# Root.net
KiCad netlist of a schematic drawn in Altium Designer
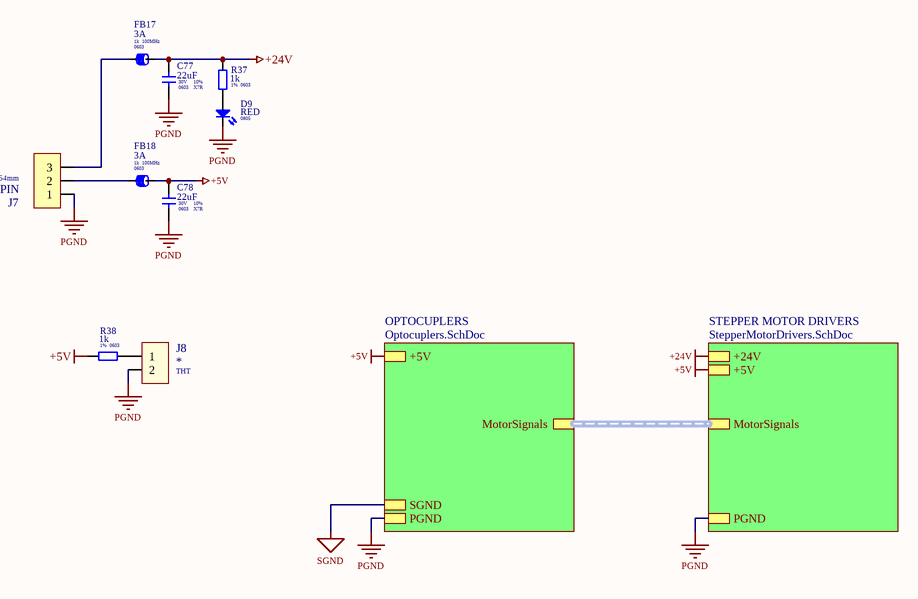
[diagram p0: Root.SchDoc]

(export (version "E")
  (design (tool "Eeschema 10.0.6"))
  (components
    (comp (ref "C77")
      (value "22uF")
      (footprint "CAPC1608X06L")
      (fields
        (field (name "DIELECTRICTYPE") "X7R")
        (field (name "VOLTAGE") "30V")
        (field (name "TOLERANT") "10%")
        (field (name "PACKAGE") "0603")
        (field (name "Comment") "22uF/30V")
      )
      (libsource (lib "unnamed") (part "C"))
    )
    (comp (ref "C78")
      (value "22uF")
      (footprint "CAPC1608X06L")
      (fields
        (field (name "DIELECTRICTYPE") "X7R")
        (field (name "VOLTAGE") "30V")
        (field (name "TOLERANT") "10%")
        (field (name "PACKAGE") "0603")
        (field (name "Comment") "22uF/30V")
      )
      (libsource (lib "unnamed") (part "C"))
    )
    (comp (ref "D9")
      (value "RED")
      (footprint "DIOMELF1608L")
      (fields (field (name "PACKAGE") "0805"))
      (libsource (lib "unnamed") (part "D_LED"))
    )
    (comp (ref "FB17")
      (value "3A")
      (footprint "INDC1608X06N")
      (description "Ferrite bead - 2-nd Symbol")
      (fields
        (field (name "MIN FREQUENCY") "100MHz")
        (field (name "IMPEDANCE") "1k")
        (field (name "PACKAGE") "0603")
      )
      (libsource (lib "unnamed") (part "FB_1"))
    )
    (comp (ref "FB18")
      (value "3A")
      (footprint "INDC1608X06L")
      (description "Ferrite bead - 2-nd Symbol")
      (fields
        (field (name "MIN FREQUENCY") "100MHz")
        (field (name "IMPEDANCE") "1k")
        (field (name "PACKAGE") "0603")
      )
      (libsource (lib "unnamed") (part "FB_1"))
    )
    (comp (ref "J7")
      (value "3PIN")
      (footprint "B3B-PH-K-S")
      (fields (field (name "PACKAGE") "2.54mm"))
      (libsource (lib "unnamed") (part "CON_3PIN"))
    )
    (comp (ref "J8")
      (value "*")
      (footprint "B2B-PH-K-S")
      (fields (field (name "ALTIUM_VALUE") "*") (field (name "PACKAGE") "THT"))
      (libsource (lib "unnamed") (part "CON_2PIN"))
    )
    (comp (ref "R37")
      (value "1k")
      (footprint "RESC1608X06L")
      (fields
        (field (name "PACKAGE") "0603")
        (field (name "TOLERANCE") "1%")
        (field (name "Comment") "1k 1%")
      )
      (libsource (lib "unnamed") (part "R"))
    )
    (comp (ref "R38")
      (value "1k")
      (footprint "RESC1608X06L")
      (fields
        (field (name "PACKAGE") "0603")
        (field (name "TOLERANCE") "1%")
        (field (name "Comment") "1k 1%")
      )
      (libsource (lib "") (part "R_1"))
    )
  )
  (nets
    (net (code "1") (name "+5V") (class "Default")
      (node (ref "C78") (pin "2") (pinfunction "2_2") (pintype "passive"))
      (node (ref "FB18") (pin "2") (pintype "passive"))
      (node (ref "R38") (pin "2") (pinfunction "2_2") (pintype "passive"))
    )
    (net (code "2") (name "+24V") (class "Default")
      (node (ref "C77") (pin "2") (pinfunction "2_2") (pintype "passive"))
      (node (ref "FB17") (pin "2") (pintype "passive"))
      (node (ref "R37") (pin "2") (pinfunction "2_2") (pintype "passive"))
    )
    (net (code "4") (name "Net-(D9-A)") (class "Default")
      (node (ref "D9") (pin "1") (pinfunction "A_1") (pintype "passive"))
      (node (ref "R37") (pin "1") (pinfunction "1_1") (pintype "passive"))
    )
    (net (code "5") (name "Net-(FB17-Pad1)") (class "Default")
      (node (ref "FB17") (pin "1") (pintype "passive"))
      (node (ref "J7") (pin "3") (pinfunction "3_3") (pintype "passive"))
    )
    (net (code "6") (name "Net-(FB18-Pad1)") (class "Default")
      (node (ref "FB18") (pin "1") (pintype "passive"))
      (node (ref "J7") (pin "2") (pinfunction "2_2") (pintype "passive"))
    )
    (net (code "7") (name "Net-(J8-Pad1)") (class "Default")
      (node (ref "J8") (pin "1") (pinfunction "1_1") (pintype "passive"))
      (node (ref "R38") (pin "1") (pinfunction "1_1") (pintype "passive"))
    )
    (net (code "8") (name "PGND") (class "Default")
      (node (ref "C77") (pin "1") (pinfunction "1_1") (pintype "passive"))
      (node (ref "C78") (pin "1") (pinfunction "1_1") (pintype "passive"))
      (node (ref "D9") (pin "2") (pinfunction "K_2") (pintype "passive"))
      (node (ref "J7") (pin "1") (pinfunction "1_1") (pintype "passive"))
      (node (ref "J8") (pin "2") (pinfunction "2_2") (pintype "passive"))
    )
  )
)
